# MOSFET.net
KiCad netlist of a schematic drawn in Altium Designer
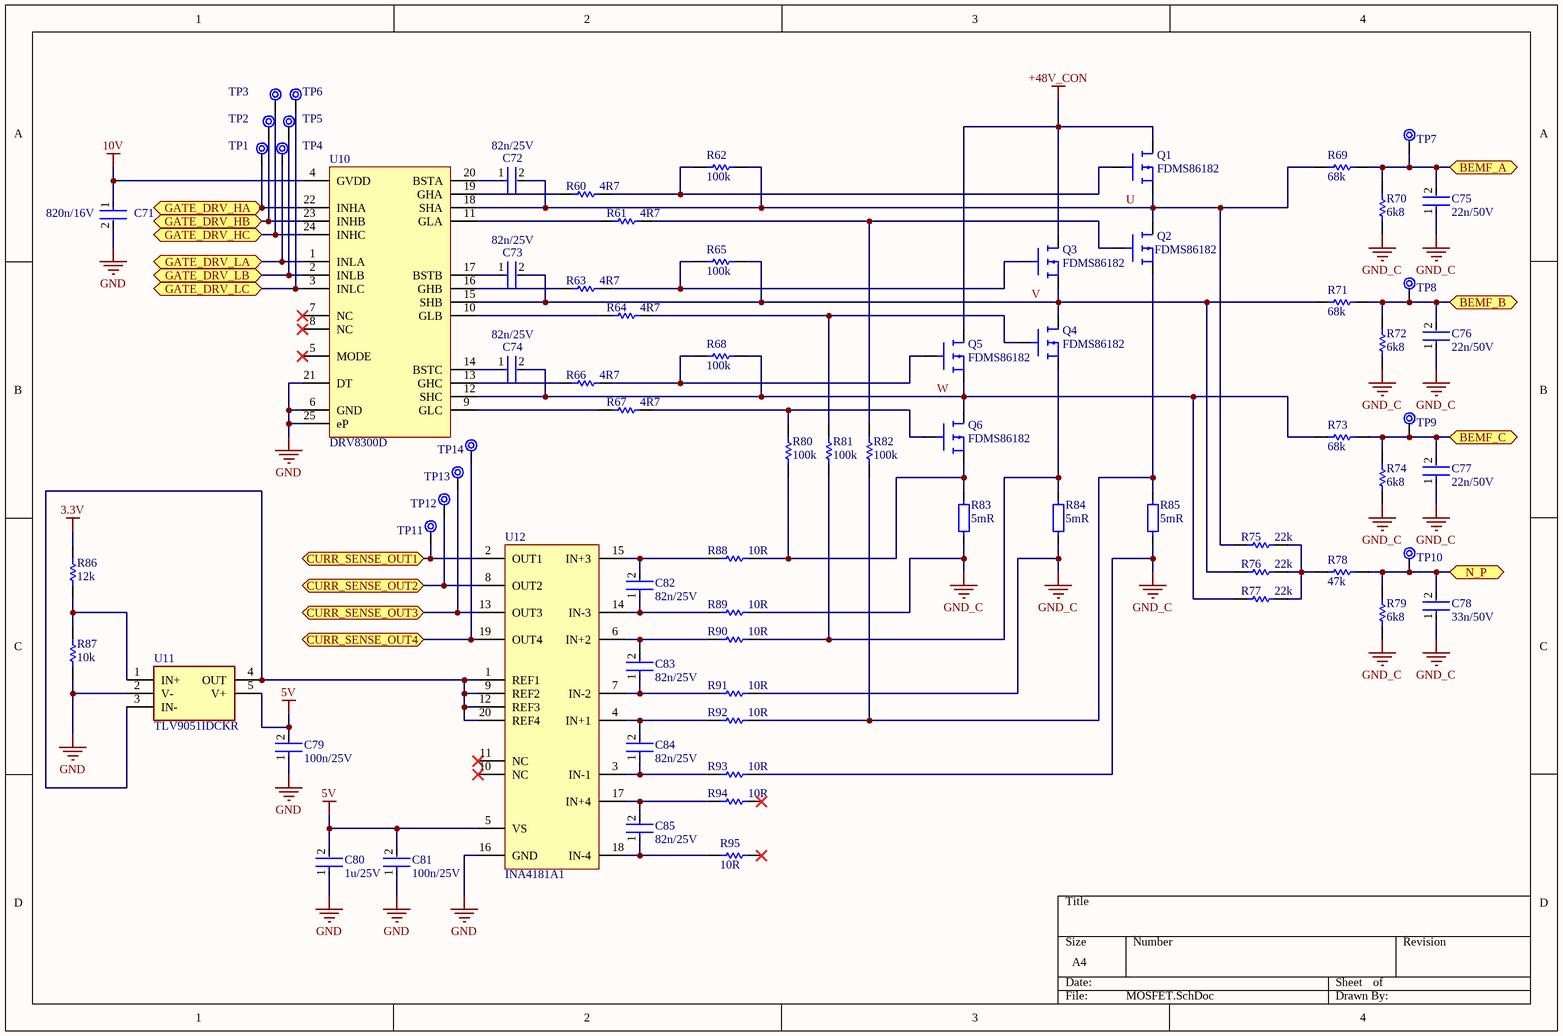
[diagram p0: MOSFET.SchDoc]

(export (version "E")
  (design (tool "Eeschema 10.0.6"))
  (components
    (comp (ref "C71")
      (value "820n/16V")
      (footprint "FP-C0805C-DN-MFG")
      (description "CAP CER 0.1UF 50V X7R 0805")
      (fields
        (field (name "MANUFACTURER PART NUMBER") "C0805C104K5RACTU")
        (field (name "MANUFACTURER") "KEMET")
      )
      (libsource (lib "Altium Content Vault") (part "b4654b650e69147ec39a6b967a45e02"))
    )
    (comp (ref "C72")
      (value "82n/25V")
      (footprint "FP-C0805C-DN-MFG")
      (description "CAP CER 0.1UF 50V X7R 0805")
      (fields
        (field (name "MANUFACTURER PART NUMBER") "C0805C104K5RACTU")
        (field (name "MANUFACTURER") "KEMET")
      )
      (libsource (lib "Altium Content Vault") (part "b4654b650e69147ec39a6b967a45e02"))
    )
    (comp (ref "C73")
      (value "82n/25V")
      (footprint "FP-C0805C-DN-MFG")
      (description "CAP CER 0.1UF 50V X7R 0805")
      (fields
        (field (name "MANUFACTURER PART NUMBER") "C0805C104K5RACTU")
        (field (name "MANUFACTURER") "KEMET")
      )
      (libsource (lib "Altium Content Vault") (part "b4654b650e69147ec39a6b967a45e02"))
    )
    (comp (ref "C74")
      (value "82n/25V")
      (footprint "FP-C0805C-DN-MFG")
      (description "CAP CER 0.1UF 50V X7R 0805")
      (fields
        (field (name "MANUFACTURER PART NUMBER") "C0805C104K5RACTU")
        (field (name "MANUFACTURER") "KEMET")
      )
      (libsource (lib "Altium Content Vault") (part "b4654b650e69147ec39a6b967a45e02"))
    )
    (comp (ref "C75")
      (value "22n/50V")
      (footprint "FP-C0805C-DN-MFG")
      (description "CAP CER 0.1UF 50V X7R 0805")
      (fields
        (field (name "MANUFACTURER PART NUMBER") "C0805C104K5RACTU")
        (field (name "MANUFACTURER") "KEMET")
      )
      (libsource (lib "Altium Content Vault") (part "b4654b650e69147ec39a6b967a45e02"))
    )
    (comp (ref "C76")
      (value "22n/50V")
      (footprint "FP-C0805C-DN-MFG")
      (description "CAP CER 0.1UF 50V X7R 0805")
      (fields
        (field (name "MANUFACTURER PART NUMBER") "C0805C104K5RACTU")
        (field (name "MANUFACTURER") "KEMET")
      )
      (libsource (lib "Altium Content Vault") (part "b4654b650e69147ec39a6b967a45e02"))
    )
    (comp (ref "C77")
      (value "22n/50V")
      (footprint "FP-C0805C-DN-MFG")
      (description "CAP CER 0.1UF 50V X7R 0805")
      (fields
        (field (name "MANUFACTURER PART NUMBER") "C0805C104K5RACTU")
        (field (name "MANUFACTURER") "KEMET")
      )
      (libsource (lib "Altium Content Vault") (part "b4654b650e69147ec39a6b967a45e02"))
    )
    (comp (ref "C78")
      (value "33n/50V")
      (footprint "FP-C0805C-DN-MFG")
      (description "CAP CER 0.1UF 50V X7R 0805")
      (fields
        (field (name "MANUFACTURER PART NUMBER") "C0805C104K5RACTU")
        (field (name "MANUFACTURER") "KEMET")
      )
      (libsource (lib "Altium Content Vault") (part "b4654b650e69147ec39a6b967a45e02"))
    )
    (comp (ref "C79")
      (value "100n/25V")
      (footprint "FP-C0805C-DN-MFG")
      (description "CAP CER 0.1UF 50V X7R 0805")
      (fields
        (field (name "MANUFACTURER PART NUMBER") "C0805C104K5RACTU")
        (field (name "MANUFACTURER") "KEMET")
      )
      (libsource (lib "Altium Content Vault") (part "b4654b650e69147ec39a6b967a45e02"))
    )
    (comp (ref "C80")
      (value "1u/25V")
      (footprint "FP-C0805C-DN-MFG")
      (description "CAP CER 0.1UF 50V X7R 0805")
      (fields
        (field (name "MANUFACTURER PART NUMBER") "C0805C104K5RACTU")
        (field (name "MANUFACTURER") "KEMET")
      )
      (libsource (lib "Altium Content Vault") (part "b4654b650e69147ec39a6b967a45e02"))
    )
    (comp (ref "C81")
      (value "100n/25V")
      (footprint "FP-C0805C-DN-MFG")
      (description "CAP CER 0.1UF 50V X7R 0805")
      (fields
        (field (name "MANUFACTURER PART NUMBER") "C0805C104K5RACTU")
        (field (name "MANUFACTURER") "KEMET")
      )
      (libsource (lib "Altium Content Vault") (part "b4654b650e69147ec39a6b967a45e02"))
    )
    (comp (ref "C82")
      (value "82n/25V")
      (footprint "FP-C0805C-DN-MFG")
      (description "CAP CER 0.1UF 50V X7R 0805")
      (fields
        (field (name "MANUFACTURER PART NUMBER") "C0805C104K5RACTU")
        (field (name "MANUFACTURER") "KEMET")
      )
      (libsource (lib "Altium Content Vault") (part "b4654b650e69147ec39a6b967a45e02"))
    )
    (comp (ref "C83")
      (value "82n/25V")
      (footprint "FP-C0805C-DN-MFG")
      (description "CAP CER 0.1UF 50V X7R 0805")
      (fields
        (field (name "MANUFACTURER PART NUMBER") "C0805C104K5RACTU")
        (field (name "MANUFACTURER") "KEMET")
      )
      (libsource (lib "Altium Content Vault") (part "b4654b650e69147ec39a6b967a45e02"))
    )
    (comp (ref "C84")
      (value "82n/25V")
      (footprint "FP-C0805C-DN-MFG")
      (description "CAP CER 0.1UF 50V X7R 0805")
      (fields
        (field (name "MANUFACTURER PART NUMBER") "C0805C104K5RACTU")
        (field (name "MANUFACTURER") "KEMET")
      )
      (libsource (lib "Altium Content Vault") (part "b4654b650e69147ec39a6b967a45e02"))
    )
    (comp (ref "C85")
      (value "82n/25V")
      (footprint "FP-C0805C-DN-MFG")
      (description "CAP CER 0.1UF 50V X7R 0805")
      (fields
        (field (name "MANUFACTURER PART NUMBER") "C0805C104K5RACTU")
        (field (name "MANUFACTURER") "KEMET")
      )
      (libsource (lib "Altium Content Vault") (part "b4654b650e69147ec39a6b967a45e02"))
    )
    (comp (ref "Q1")
      (value "FDMS86182")
      (footprint "FDMS86182")
      (description "MOSFET PTNG 100/20V Nch Power Trench MOSFET")
      (fields (field (name "MANUFACTURER") "Onsemi"))
      (libsource (lib "OTHER") (part "FDMS86182"))
    )
    (comp (ref "Q2")
      (value "FDMS86182")
      (footprint "FDMS86182")
      (description "MOSFET PTNG 100/20V Nch Power Trench MOSFET")
      (fields (field (name "MANUFACTURER") "Onsemi"))
      (libsource (lib "OTHER") (part "FDMS86182"))
    )
    (comp (ref "Q3")
      (value "FDMS86182")
      (footprint "FDMS86182")
      (description "MOSFET PTNG 100/20V Nch Power Trench MOSFET")
      (fields (field (name "MANUFACTURER") "Onsemi"))
      (libsource (lib "OTHER") (part "FDMS86182"))
    )
    (comp (ref "Q4")
      (value "FDMS86182")
      (footprint "FDMS86182")
      (description "MOSFET PTNG 100/20V Nch Power Trench MOSFET")
      (fields (field (name "MANUFACTURER") "Onsemi"))
      (libsource (lib "OTHER") (part "FDMS86182"))
    )
    (comp (ref "Q5")
      (value "FDMS86182")
      (footprint "FDMS86182")
      (description "MOSFET PTNG 100/20V Nch Power Trench MOSFET")
      (fields (field (name "MANUFACTURER") "Onsemi"))
      (libsource (lib "OTHER") (part "FDMS86182"))
    )
    (comp (ref "Q6")
      (value "FDMS86182")
      (footprint "FDMS86182")
      (description "MOSFET PTNG 100/20V Nch Power Trench MOSFET")
      (fields (field (name "MANUFACTURER") "Onsemi"))
      (libsource (lib "OTHER") (part "FDMS86182"))
    )
    (comp (ref "R60")
      (value "4R7")
      (footprint "RESC2013X50X30LL20T20")
      (description "0805")
      (fields (field (name "MANUFACTURER") "Vishay Dale") (field (name "PART NUMBER") "CRCW08050000Z0EA"))
      (libsource (lib "Altium Content Vault") (part "RES"))
    )
    (comp (ref "R61")
      (value "4R7")
      (footprint "RESC2013X50X30LL20T20")
      (description "0805")
      (fields (field (name "MANUFACTURER") "Vishay Dale") (field (name "PART NUMBER") "CRCW08050000Z0EA"))
      (libsource (lib "Altium Content Vault") (part "RES"))
    )
    (comp (ref "R62")
      (value "100k")
      (footprint "RESC2013X50X30LL20T20")
      (description "0805")
      (fields (field (name "MANUFACTURER") "Vishay Dale") (field (name "PART NUMBER") "CRCW08050000Z0EA"))
      (libsource (lib "Altium Content Vault") (part "RES"))
    )
    (comp (ref "R63")
      (value "4R7")
      (footprint "RESC2013X50X30LL20T20")
      (description "0805")
      (fields (field (name "MANUFACTURER") "Vishay Dale") (field (name "PART NUMBER") "CRCW08050000Z0EA"))
      (libsource (lib "Altium Content Vault") (part "RES"))
    )
    (comp (ref "R64")
      (value "4R7")
      (footprint "RESC2013X50X30LL20T20")
      (description "0805")
      (fields (field (name "MANUFACTURER") "Vishay Dale") (field (name "PART NUMBER") "CRCW08050000Z0EA"))
      (libsource (lib "Altium Content Vault") (part "RES"))
    )
    (comp (ref "R65")
      (value "100k")
      (footprint "RESC2013X50X30LL20T20")
      (description "0805")
      (fields (field (name "MANUFACTURER") "Vishay Dale") (field (name "PART NUMBER") "CRCW08050000Z0EA"))
      (libsource (lib "Altium Content Vault") (part "RES"))
    )
    (comp (ref "R66")
      (value "4R7")
      (footprint "RESC2013X50X30LL20T20")
      (description "0805")
      (fields (field (name "MANUFACTURER") "Vishay Dale") (field (name "PART NUMBER") "CRCW08050000Z0EA"))
      (libsource (lib "Altium Content Vault") (part "RES"))
    )
    (comp (ref "R67")
      (value "4R7")
      (footprint "RESC2013X50X30LL20T20")
      (description "0805")
      (fields (field (name "MANUFACTURER") "Vishay Dale") (field (name "PART NUMBER") "CRCW08050000Z0EA"))
      (libsource (lib "Altium Content Vault") (part "RES"))
    )
    (comp (ref "R68")
      (value "100k")
      (footprint "RESC2013X50X30LL20T20")
      (description "0805")
      (fields (field (name "MANUFACTURER") "Vishay Dale") (field (name "PART NUMBER") "CRCW08050000Z0EA"))
      (libsource (lib "Altium Content Vault") (part "RES"))
    )
    (comp (ref "R69")
      (value "68k")
      (footprint "RESC2013X50X30LL20T20")
      (description "0805")
      (fields (field (name "MANUFACTURER") "Vishay Dale") (field (name "PART NUMBER") "CRCW08050000Z0EA"))
      (libsource (lib "Altium Content Vault") (part "RES"))
    )
    (comp (ref "R70")
      (value "6k8")
      (footprint "RESC2013X50X30LL20T20")
      (description "0805")
      (fields (field (name "MANUFACTURER") "Vishay Dale") (field (name "PART NUMBER") "CRCW08050000Z0EA"))
      (libsource (lib "Altium Content Vault") (part "RES"))
    )
    (comp (ref "R71")
      (value "68k")
      (footprint "RESC2013X50X30LL20T20")
      (description "0805")
      (fields (field (name "MANUFACTURER") "Vishay Dale") (field (name "PART NUMBER") "CRCW08050000Z0EA"))
      (libsource (lib "Altium Content Vault") (part "RES"))
    )
    (comp (ref "R72")
      (value "6k8")
      (footprint "RESC2013X50X30LL20T20")
      (description "0805")
      (fields (field (name "MANUFACTURER") "Vishay Dale") (field (name "PART NUMBER") "CRCW08050000Z0EA"))
      (libsource (lib "Altium Content Vault") (part "RES"))
    )
    (comp (ref "R73")
      (value "68k")
      (footprint "RESC2013X50X30LL20T20")
      (description "0805")
      (fields (field (name "MANUFACTURER") "Vishay Dale") (field (name "PART NUMBER") "CRCW08050000Z0EA"))
      (libsource (lib "Altium Content Vault") (part "RES"))
    )
    (comp (ref "R74")
      (value "6k8")
      (footprint "RESC2013X50X30LL20T20")
      (description "0805")
      (fields (field (name "MANUFACTURER") "Vishay Dale") (field (name "PART NUMBER") "CRCW08050000Z0EA"))
      (libsource (lib "Altium Content Vault") (part "RES"))
    )
    (comp (ref "R75")
      (value "22k")
      (footprint "RESC2013X50X30LL20T20")
      (description "0805")
      (fields (field (name "MANUFACTURER") "Vishay Dale") (field (name "PART NUMBER") "CRCW08050000Z0EA"))
      (libsource (lib "Altium Content Vault") (part "RES"))
    )
    (comp (ref "R76")
      (value "22k")
      (footprint "RESC2013X50X30LL20T20")
      (description "0805")
      (fields (field (name "MANUFACTURER") "Vishay Dale") (field (name "PART NUMBER") "CRCW08050000Z0EA"))
      (libsource (lib "Altium Content Vault") (part "RES"))
    )
    (comp (ref "R77")
      (value "22k")
      (footprint "RESC2013X50X30LL20T20")
      (description "0805")
      (fields (field (name "MANUFACTURER") "Vishay Dale") (field (name "PART NUMBER") "CRCW08050000Z0EA"))
      (libsource (lib "Altium Content Vault") (part "RES"))
    )
    (comp (ref "R78")
      (value "47k")
      (footprint "RESC2013X50X30LL20T20")
      (description "0805")
      (fields (field (name "MANUFACTURER") "Vishay Dale") (field (name "PART NUMBER") "CRCW08050000Z0EA"))
      (libsource (lib "Altium Content Vault") (part "RES"))
    )
    (comp (ref "R79")
      (value "6k8")
      (footprint "RESC2013X50X30LL20T20")
      (description "0805")
      (fields (field (name "MANUFACTURER") "Vishay Dale") (field (name "PART NUMBER") "CRCW08050000Z0EA"))
      (libsource (lib "Altium Content Vault") (part "RES"))
    )
    (comp (ref "R80")
      (value "100k")
      (footprint "RESC2013X50X30LL20T20")
      (description "0805")
      (fields (field (name "MANUFACTURER") "Vishay Dale") (field (name "PART NUMBER") "CRCW08050000Z0EA"))
      (libsource (lib "Altium Content Vault") (part "RES"))
    )
    (comp (ref "R81")
      (value "100k")
      (footprint "RESC2013X50X30LL20T20")
      (description "0805")
      (fields (field (name "MANUFACTURER") "Vishay Dale") (field (name "PART NUMBER") "CRCW08050000Z0EA"))
      (libsource (lib "Altium Content Vault") (part "RES"))
    )
    (comp (ref "R82")
      (value "100k")
      (footprint "RESC2013X50X30LL20T20")
      (description "0805")
      (fields (field (name "MANUFACTURER") "Vishay Dale") (field (name "PART NUMBER") "CRCW08050000Z0EA"))
      (libsource (lib "Altium Content Vault") (part "RES"))
    )
    (comp (ref "R83")
      (value "5mR")
      (footprint "RESC6432X08N")
      (description "Current Sense Resistors - SMD 0.005ohms 1% 75PPM")
      (fields (field (name "MANUFACTURER") "Vishay") (field (name "PART NUMBER") "CRCW0402100RFKEDC"))
      (libsource (lib "RESISTOR") (part "RES/5mR/1%/2512"))
    )
    (comp (ref "R84")
      (value "5mR")
      (footprint "RESC6432X08N")
      (description "Current Sense Resistors - SMD 0.005ohms 1% 75PPM")
      (fields (field (name "MANUFACTURER") "Vishay") (field (name "PART NUMBER") "CRCW0402100RFKEDC"))
      (libsource (lib "RESISTOR") (part "RES/5mR/1%/2512"))
    )
    (comp (ref "R85")
      (value "5mR")
      (footprint "RESC6432X08N")
      (description "Current Sense Resistors - SMD 0.005ohms 1% 75PPM")
      (fields (field (name "MANUFACTURER") "Vishay") (field (name "PART NUMBER") "CRCW0402100RFKEDC"))
      (libsource (lib "RESISTOR") (part "RES/5mR/1%/2512"))
    )
    (comp (ref "R86")
      (value "12k")
      (footprint "RESC2013X50X30LL20T20")
      (description "0805")
      (fields (field (name "MANUFACTURER") "Vishay Dale") (field (name "PART NUMBER") "CRCW08050000Z0EA"))
      (libsource (lib "Altium Content Vault") (part "RES"))
    )
    (comp (ref "R87")
      (value "10k")
      (footprint "RESC2013X50X30LL20T20")
      (description "0805")
      (fields (field (name "MANUFACTURER") "Vishay Dale") (field (name "PART NUMBER") "CRCW08050000Z0EA"))
      (libsource (lib "Altium Content Vault") (part "RES"))
    )
    (comp (ref "R88")
      (value "10R")
      (footprint "RESC2013X50X30LL20T20")
      (description "0805")
      (fields (field (name "MANUFACTURER") "Vishay Dale") (field (name "PART NUMBER") "CRCW08050000Z0EA"))
      (libsource (lib "Altium Content Vault") (part "RES"))
    )
    (comp (ref "R89")
      (value "10R")
      (footprint "RESC2013X50X30LL20T20")
      (description "0805")
      (fields (field (name "MANUFACTURER") "Vishay Dale") (field (name "PART NUMBER") "CRCW08050000Z0EA"))
      (libsource (lib "Altium Content Vault") (part "RES"))
    )
    (comp (ref "R90")
      (value "10R")
      (footprint "RESC2013X50X30LL20T20")
      (description "0805")
      (fields (field (name "MANUFACTURER") "Vishay Dale") (field (name "PART NUMBER") "CRCW08050000Z0EA"))
      (libsource (lib "Altium Content Vault") (part "RES"))
    )
    (comp (ref "R91")
      (value "10R")
      (footprint "RESC2013X50X30LL20T20")
      (description "0805")
      (fields (field (name "MANUFACTURER") "Vishay Dale") (field (name "PART NUMBER") "CRCW08050000Z0EA"))
      (libsource (lib "Altium Content Vault") (part "RES"))
    )
    (comp (ref "R92")
      (value "10R")
      (footprint "RESC2013X50X30LL20T20")
      (description "0805")
      (fields (field (name "MANUFACTURER") "Vishay Dale") (field (name "PART NUMBER") "CRCW08050000Z0EA"))
      (libsource (lib "Altium Content Vault") (part "RES"))
    )
    (comp (ref "R93")
      (value "10R")
      (footprint "RESC2013X50X30LL20T20")
      (description "0805")
      (fields (field (name "MANUFACTURER") "Vishay Dale") (field (name "PART NUMBER") "CRCW08050000Z0EA"))
      (libsource (lib "Altium Content Vault") (part "RES"))
    )
    (comp (ref "R94")
      (value "10R")
      (footprint "RESC2013X50X30LL20T20")
      (description "0805")
      (fields (field (name "MANUFACTURER") "Vishay Dale") (field (name "PART NUMBER") "CRCW08050000Z0EA"))
      (libsource (lib "Altium Content Vault") (part "RES"))
    )
    (comp (ref "R95")
      (value "10R")
      (footprint "RESC2013X50X30LL20T20")
      (description "0805")
      (fields (field (name "MANUFACTURER") "Vishay Dale") (field (name "PART NUMBER") "CRCW08050000Z0EA"))
      (libsource (lib "Altium Content Vault") (part "RES"))
    )
    (comp (ref "TP1")
      (value "Test Point 1mm")
      (footprint "Pad 1mm")
      (libsource (lib "OTHER") (part "Test Point 1mm"))
    )
    (comp (ref "TP2")
      (value "Test Point 1mm")
      (footprint "Pad 1mm")
      (libsource (lib "OTHER") (part "Test Point 1mm"))
    )
    (comp (ref "TP3")
      (value "Test Point 1mm")
      (footprint "Pad 1mm")
      (libsource (lib "OTHER") (part "Test Point 1mm"))
    )
    (comp (ref "TP4")
      (value "Test Point 1mm")
      (footprint "Pad 1mm")
      (libsource (lib "OTHER") (part "Test Point 1mm"))
    )
    (comp (ref "TP5")
      (value "Test Point 1mm")
      (footprint "Pad 1mm")
      (libsource (lib "OTHER") (part "Test Point 1mm"))
    )
    (comp (ref "TP6")
      (value "Test Point 1mm")
      (footprint "Pad 1mm")
      (libsource (lib "OTHER") (part "Test Point 1mm"))
    )
    (comp (ref "TP7")
      (value "Test Point 1mm")
      (footprint "Pad 1mm")
      (libsource (lib "OTHER") (part "Test Point 1mm"))
    )
    (comp (ref "TP8")
      (value "Test Point 1mm")
      (footprint "Pad 1mm")
      (libsource (lib "OTHER") (part "Test Point 1mm"))
    )
    (comp (ref "TP9")
      (value "Test Point 1mm")
      (footprint "Pad 1mm")
      (libsource (lib "OTHER") (part "Test Point 1mm"))
    )
    (comp (ref "TP10")
      (value "Test Point 1mm")
      (footprint "Pad 1mm")
      (libsource (lib "OTHER") (part "Test Point 1mm"))
    )
    (comp (ref "TP11")
      (value "Test Point 1mm")
      (footprint "Pad 1mm")
      (libsource (lib "OTHER") (part "Test Point 1mm"))
    )
    (comp (ref "TP12")
      (value "Test Point 1mm")
      (footprint "Pad 1mm")
      (libsource (lib "OTHER") (part "Test Point 1mm"))
    )
    (comp (ref "TP13")
      (value "Test Point 1mm")
      (footprint "Pad 1mm")
      (libsource (lib "OTHER") (part "Test Point 1mm"))
    )
    (comp (ref "TP14")
      (value "Test Point 1mm")
      (footprint "Pad 1mm")
      (libsource (lib "OTHER") (part "Test Point 1mm"))
    )
    (comp (ref "U10")
      (value "DRV8300D")
      (footprint "PQFN50P400X400X100_HS-25N")
      (description "Gate Drivers 100-V max simple 3-phase gate driver with bootstrap diodes 24-VQFN -40 to 125")
      (fields (field (name "MANUFACTURER") "Texas Instruments") (field (name "PART NUMBER") "DRV8300DRGER"))
      (libsource (lib "IC") (part "DRV8300D"))
    )
    (comp (ref "U11")
      (value "TLV9051IDCKR")
      (footprint "SOT65P210X110-5N")
      (description "Operational Amplifiers - Op Amps OPAMP")
      (fields (field (name "MOUSER PART NUMBER") "595-TLV9051IDCKR"))
      (libsource (lib "TLV9051IDCKR_LeveLConv") (part "TLV9051IDCKR"))
    )
    (comp (ref "U12")
      (value "INA4181A1")
      (footprint "TSOP65P640X120-20N")
      (fields (field (name "MANUFACTURER") "Texas Instruments") (field (name "PART NUMBER") "INA4181A1IPWR"))
      (libsource (lib "IC") (part "INA4181A1"))
    )
  )
  (nets
    (net (code "1") (name "+48V_CON") (class "Default")
      (node (ref "Q1") (pin "D") (pinfunction "D_D") (pintype "passive"))
      (node (ref "Q3") (pin "D") (pinfunction "D_D") (pintype "passive"))
      (node (ref "Q5") (pin "D") (pinfunction "D_D") (pintype "passive"))
    )
    (net (code "2") (name "/BEMF_A") (class "Default")
      (node (ref "C75") (pin "2") (pinfunction "2_2") (pintype "passive"))
      (node (ref "R69") (pin "1") (pinfunction "1_1") (pintype "passive"))
      (node (ref "R70") (pin "1") (pinfunction "1_1") (pintype "passive"))
      (node (ref "TP7") (pin "1") (pinfunction "1_1") (pintype "passive"))
    )
    (net (code "3") (name "/BEMF_B") (class "Default")
      (node (ref "C76") (pin "2") (pinfunction "2_2") (pintype "passive"))
      (node (ref "R71") (pin "1") (pinfunction "1_1") (pintype "passive"))
      (node (ref "R72") (pin "1") (pinfunction "1_1") (pintype "passive"))
      (node (ref "TP8") (pin "1") (pinfunction "1_1") (pintype "passive"))
    )
    (net (code "4") (name "/BEMF_C") (class "Default")
      (node (ref "C77") (pin "2") (pinfunction "2_2") (pintype "passive"))
      (node (ref "R73") (pin "1") (pinfunction "1_1") (pintype "passive"))
      (node (ref "R74") (pin "1") (pinfunction "1_1") (pintype "passive"))
      (node (ref "TP9") (pin "1") (pinfunction "1_1") (pintype "passive"))
    )
    (net (code "5") (name "/CURR_SENSE_OUT1") (class "Default")
      (node (ref "TP11") (pin "1") (pinfunction "1_1") (pintype "passive"))
      (node (ref "U12") (pin "2") (pinfunction "OUT1_2") (pintype "passive"))
    )
    (net (code "6") (name "/CURR_SENSE_OUT2") (class "Default")
      (node (ref "TP12") (pin "1") (pinfunction "1_1") (pintype "passive"))
      (node (ref "U12") (pin "8") (pinfunction "OUT2_8") (pintype "passive"))
    )
    (net (code "7") (name "/CURR_SENSE_OUT3") (class "Default")
      (node (ref "TP13") (pin "1") (pinfunction "1_1") (pintype "passive"))
      (node (ref "U12") (pin "13") (pinfunction "OUT3_13") (pintype "passive"))
    )
    (net (code "8") (name "/CURR_SENSE_OUT4") (class "Default")
      (node (ref "TP14") (pin "1") (pinfunction "1_1") (pintype "passive"))
      (node (ref "U12") (pin "19") (pinfunction "OUT4_19") (pintype "passive"))
    )
    (net (code "9") (name "/GATE_DRV_HA") (class "Default")
      (node (ref "TP1") (pin "1") (pinfunction "1_1") (pintype "passive"))
      (node (ref "U10") (pin "22") (pinfunction "INHA_22") (pintype "passive"))
    )
    (net (code "10") (name "/GATE_DRV_HB") (class "Default")
      (node (ref "TP2") (pin "1") (pinfunction "1_1") (pintype "passive"))
      (node (ref "U10") (pin "23") (pinfunction "INHB_23") (pintype "passive"))
    )
    (net (code "11") (name "/GATE_DRV_HC") (class "Default")
      (node (ref "TP3") (pin "1") (pinfunction "1_1") (pintype "passive"))
      (node (ref "U10") (pin "24") (pinfunction "INHC_24") (pintype "passive"))
    )
    (net (code "12") (name "/GATE_DRV_LA") (class "Default")
      (node (ref "TP4") (pin "1") (pinfunction "1_1") (pintype "passive"))
      (node (ref "U10") (pin "1") (pinfunction "INLA_1") (pintype "passive"))
    )
    (net (code "13") (name "/GATE_DRV_LB") (class "Default")
      (node (ref "TP5") (pin "1") (pinfunction "1_1") (pintype "passive"))
      (node (ref "U10") (pin "2") (pinfunction "INLB_2") (pintype "passive"))
    )
    (net (code "14") (name "/GATE_DRV_LC") (class "Default")
      (node (ref "TP6") (pin "1") (pinfunction "1_1") (pintype "passive"))
      (node (ref "U10") (pin "3") (pinfunction "INLC_3") (pintype "passive"))
    )
    (net (code "15") (name "/N_P") (class "Default")
      (node (ref "C78") (pin "2") (pinfunction "2_2") (pintype "passive"))
      (node (ref "R78") (pin "1") (pinfunction "1_1") (pintype "passive"))
      (node (ref "R79") (pin "1") (pinfunction "1_1") (pintype "passive"))
      (node (ref "TP10") (pin "1") (pinfunction "1_1") (pintype "passive"))
    )
    (net (code "16") (name "/U") (class "Default")
      (node (ref "C72") (pin "2") (pinfunction "2_2") (pintype "passive"))
      (node (ref "Q1") (pin "S") (pinfunction "S_S") (pintype "passive"))
      (node (ref "Q2") (pin "D") (pinfunction "D_D") (pintype "passive"))
      (node (ref "R62") (pin "1") (pinfunction "1_1") (pintype "passive"))
      (node (ref "R69") (pin "2") (pinfunction "2_2") (pintype "passive"))
      (node (ref "R75") (pin "2") (pinfunction "2_2") (pintype "passive"))
      (node (ref "U10") (pin "18") (pinfunction "SHA_18") (pintype "passive"))
    )
    (net (code "17") (name "/V") (class "Default")
      (node (ref "C73") (pin "2") (pinfunction "2_2") (pintype "passive"))
      (node (ref "Q3") (pin "S") (pinfunction "S_S") (pintype "passive"))
      (node (ref "Q4") (pin "D") (pinfunction "D_D") (pintype "passive"))
      (node (ref "R65") (pin "1") (pinfunction "1_1") (pintype "passive"))
      (node (ref "R71") (pin "2") (pinfunction "2_2") (pintype "passive"))
      (node (ref "R76") (pin "2") (pinfunction "2_2") (pintype "passive"))
      (node (ref "U10") (pin "15") (pinfunction "SHB_15") (pintype "passive"))
    )
    (net (code "18") (name "/W") (class "Default")
      (node (ref "C74") (pin "2") (pinfunction "2_2") (pintype "passive"))
      (node (ref "Q5") (pin "S") (pinfunction "S_S") (pintype "passive"))
      (node (ref "Q6") (pin "D") (pinfunction "D_D") (pintype "passive"))
      (node (ref "R68") (pin "1") (pinfunction "1_1") (pintype "passive"))
      (node (ref "R73") (pin "2") (pinfunction "2_2") (pintype "passive"))
      (node (ref "R77") (pin "2") (pinfunction "2_2") (pintype "passive"))
      (node (ref "U10") (pin "12") (pinfunction "SHC_12") (pintype "passive"))
    )
    (net (code "19") (name "3.3V") (class "Default")
      (node (ref "R86") (pin "1") (pinfunction "1_1") (pintype "passive"))
    )
    (net (code "20") (name "5V") (class "Default")
      (node (ref "C79") (pin "2") (pinfunction "2_2") (pintype "passive"))
      (node (ref "C80") (pin "2") (pinfunction "2_2") (pintype "passive"))
      (node (ref "C81") (pin "2") (pinfunction "2_2") (pintype "passive"))
      (node (ref "U11") (pin "5") (pinfunction "V+_5") (pintype "passive"))
      (node (ref "U12") (pin "5") (pinfunction "VS_5") (pintype "passive"))
    )
    (net (code "21") (name "10V") (class "Default")
      (node (ref "C71") (pin "1") (pinfunction "1_1") (pintype "passive"))
      (node (ref "U10") (pin "4") (pinfunction "GVDD_4") (pintype "passive"))
    )
    (net (code "22") (name "GND") (class "Default")
      (node (ref "C71") (pin "2") (pinfunction "2_2") (pintype "passive"))
      (node (ref "C79") (pin "1") (pinfunction "1_1") (pintype "passive"))
      (node (ref "C80") (pin "1") (pinfunction "1_1") (pintype "passive"))
      (node (ref "C81") (pin "1") (pinfunction "1_1") (pintype "passive"))
      (node (ref "R87") (pin "2") (pinfunction "2_2") (pintype "passive"))
      (node (ref "U10") (pin "21") (pinfunction "DT_21") (pintype "passive"))
      (node (ref "U10") (pin "25") (pinfunction "eP_25") (pintype "passive"))
      (node (ref "U10") (pin "6") (pinfunction "GND_6") (pintype "passive"))
      (node (ref "U11") (pin "2") (pinfunction "V-_2") (pintype "passive"))
      (node (ref "U12") (pin "16") (pinfunction "GND_16") (pintype "passive"))
    )
    (net (code "23") (name "GND_C") (class "Default")
      (node (ref "C75") (pin "1") (pinfunction "1_1") (pintype "passive"))
      (node (ref "C76") (pin "1") (pinfunction "1_1") (pintype "passive"))
      (node (ref "C77") (pin "1") (pinfunction "1_1") (pintype "passive"))
      (node (ref "C78") (pin "1") (pinfunction "1_1") (pintype "passive"))
      (node (ref "R70") (pin "2") (pinfunction "2_2") (pintype "passive"))
      (node (ref "R72") (pin "2") (pinfunction "2_2") (pintype "passive"))
      (node (ref "R74") (pin "2") (pinfunction "2_2") (pintype "passive"))
      (node (ref "R79") (pin "2") (pinfunction "2_2") (pintype "passive"))
      (node (ref "R83") (pin "1") (pinfunction "1_1") (pintype "passive"))
      (node (ref "R84") (pin "1") (pinfunction "1_1") (pintype "passive"))
      (node (ref "R85") (pin "1") (pinfunction "1_1") (pintype "passive"))
      (node (ref "R89") (pin "1") (pinfunction "1_1") (pintype "passive"))
      (node (ref "R91") (pin "1") (pinfunction "1_1") (pintype "passive"))
      (node (ref "R93") (pin "1") (pinfunction "1_1") (pintype "passive"))
    )
    (net (code "24") (name "Net-(Q1-PadG)") (class "Default")
      (node (ref "Q1") (pin "G") (pinfunction "G_G") (pintype "passive"))
      (node (ref "R60") (pin "1") (pinfunction "1_1") (pintype "passive"))
      (node (ref "R62") (pin "2") (pinfunction "2_2") (pintype "passive"))
    )
    (net (code "25") (name "Net-(Q2-PadG)") (class "Default")
      (node (ref "Q2") (pin "G") (pinfunction "G_G") (pintype "passive"))
      (node (ref "R61") (pin "1") (pinfunction "1_1") (pintype "passive"))
      (node (ref "R82") (pin "1") (pinfunction "1_1") (pintype "passive"))
    )
    (net (code "26") (name "Net-(Q2-PadS)") (class "Default")
      (node (ref "Q2") (pin "S") (pinfunction "S_S") (pintype "passive"))
      (node (ref "R82") (pin "2") (pinfunction "2_2") (pintype "passive"))
      (node (ref "R85") (pin "2") (pinfunction "2_2") (pintype "passive"))
      (node (ref "R92") (pin "1") (pinfunction "1_1") (pintype "passive"))
    )
    (net (code "27") (name "Net-(Q3-PadG)") (class "Default")
      (node (ref "Q3") (pin "G") (pinfunction "G_G") (pintype "passive"))
      (node (ref "R63") (pin "1") (pinfunction "1_1") (pintype "passive"))
      (node (ref "R65") (pin "2") (pinfunction "2_2") (pintype "passive"))
    )
    (net (code "28") (name "Net-(Q4-PadG)") (class "Default")
      (node (ref "Q4") (pin "G") (pinfunction "G_G") (pintype "passive"))
      (node (ref "R64") (pin "1") (pinfunction "1_1") (pintype "passive"))
      (node (ref "R81") (pin "1") (pinfunction "1_1") (pintype "passive"))
    )
    (net (code "29") (name "Net-(Q4-PadS)") (class "Default")
      (node (ref "Q4") (pin "S") (pinfunction "S_S") (pintype "passive"))
      (node (ref "R81") (pin "2") (pinfunction "2_2") (pintype "passive"))
      (node (ref "R84") (pin "2") (pinfunction "2_2") (pintype "passive"))
      (node (ref "R90") (pin "1") (pinfunction "1_1") (pintype "passive"))
    )
    (net (code "30") (name "Net-(Q5-PadG)") (class "Default")
      (node (ref "Q5") (pin "G") (pinfunction "G_G") (pintype "passive"))
      (node (ref "R66") (pin "1") (pinfunction "1_1") (pintype "passive"))
      (node (ref "R68") (pin "2") (pinfunction "2_2") (pintype "passive"))
    )
    (net (code "31") (name "Net-(Q6-PadG)") (class "Default")
      (node (ref "Q6") (pin "G") (pinfunction "G_G") (pintype "passive"))
      (node (ref "R67") (pin "1") (pinfunction "1_1") (pintype "passive"))
      (node (ref "R80") (pin "1") (pinfunction "1_1") (pintype "passive"))
    )
    (net (code "32") (name "Net-(Q6-PadS)") (class "Default")
      (node (ref "Q6") (pin "S") (pinfunction "S_S") (pintype "passive"))
      (node (ref "R80") (pin "2") (pinfunction "2_2") (pintype "passive"))
      (node (ref "R83") (pin "2") (pinfunction "2_2") (pintype "passive"))
      (node (ref "R88") (pin "1") (pinfunction "1_1") (pintype "passive"))
    )
    (net (code "33") (name "Net-(R75-Pad1)") (class "Default")
      (node (ref "R75") (pin "1") (pinfunction "1_1") (pintype "passive"))
      (node (ref "R76") (pin "1") (pinfunction "1_1") (pintype "passive"))
      (node (ref "R77") (pin "1") (pinfunction "1_1") (pintype "passive"))
      (node (ref "R78") (pin "2") (pinfunction "2_2") (pintype "passive"))
    )
    (net (code "34") (name "Net-(U10-BSTA)") (class "Default")
      (node (ref "C72") (pin "1") (pinfunction "1_1") (pintype "passive"))
      (node (ref "U10") (pin "20") (pinfunction "BSTA_20") (pintype "passive"))
    )
    (net (code "35") (name "Net-(U10-BSTB)") (class "Default")
      (node (ref "C73") (pin "1") (pinfunction "1_1") (pintype "passive"))
      (node (ref "U10") (pin "17") (pinfunction "BSTB_17") (pintype "passive"))
    )
    (net (code "36") (name "Net-(U10-BSTC)") (class "Default")
      (node (ref "C74") (pin "1") (pinfunction "1_1") (pintype "passive"))
      (node (ref "U10") (pin "14") (pinfunction "BSTC_14") (pintype "passive"))
    )
    (net (code "37") (name "Net-(U10-GHA)") (class "Default")
      (node (ref "R60") (pin "2") (pinfunction "2_2") (pintype "passive"))
      (node (ref "U10") (pin "19") (pinfunction "GHA_19") (pintype "passive"))
    )
    (net (code "38") (name "Net-(U10-GHB)") (class "Default")
      (node (ref "R63") (pin "2") (pinfunction "2_2") (pintype "passive"))
      (node (ref "U10") (pin "16") (pinfunction "GHB_16") (pintype "passive"))
    )
    (net (code "39") (name "Net-(U10-GHC)") (class "Default")
      (node (ref "R66") (pin "2") (pinfunction "2_2") (pintype "passive"))
      (node (ref "U10") (pin "13") (pinfunction "GHC_13") (pintype "passive"))
    )
    (net (code "40") (name "Net-(U10-GLA)") (class "Default")
      (node (ref "R61") (pin "2") (pinfunction "2_2") (pintype "passive"))
      (node (ref "U10") (pin "11") (pinfunction "GLA_11") (pintype "passive"))
    )
    (net (code "41") (name "Net-(U10-GLB)") (class "Default")
      (node (ref "R64") (pin "2") (pinfunction "2_2") (pintype "passive"))
      (node (ref "U10") (pin "10") (pinfunction "GLB_10") (pintype "passive"))
    )
    (net (code "42") (name "Net-(U10-GLC)") (class "Default")
      (node (ref "R67") (pin "2") (pinfunction "2_2") (pintype "passive"))
      (node (ref "U10") (pin "9") (pinfunction "GLC_9") (pintype "passive"))
    )
    (net (code "43") (name "Net-(U11-IN+)") (class "Default")
      (node (ref "R86") (pin "2") (pinfunction "2_2") (pintype "passive"))
      (node (ref "R87") (pin "1") (pinfunction "1_1") (pintype "passive"))
      (node (ref "U11") (pin "1") (pinfunction "IN+_1") (pintype "passive"))
    )
    (net (code "44") (name "Net-(U11-IN-)") (class "Default")
      (node (ref "U11") (pin "3") (pinfunction "IN-_3") (pintype "passive"))
      (node (ref "U11") (pin "4") (pinfunction "OUT_4") (pintype "passive"))
      (node (ref "U12") (pin "1") (pinfunction "REF1_1") (pintype "passive"))
      (node (ref "U12") (pin "12") (pinfunction "REF3_12") (pintype "passive"))
      (node (ref "U12") (pin "20") (pinfunction "REF4_20") (pintype "passive"))
      (node (ref "U12") (pin "9") (pinfunction "REF2_9") (pintype "passive"))
    )
    (net (code "45") (name "Net-(U12-IN+1)") (class "Default")
      (node (ref "C84") (pin "2") (pinfunction "2_2") (pintype "passive"))
      (node (ref "R92") (pin "2") (pinfunction "2_2") (pintype "passive"))
      (node (ref "U12") (pin "4") (pinfunction "IN+1_4") (pintype "passive"))
    )
    (net (code "46") (name "Net-(U12-IN+2)") (class "Default")
      (node (ref "C83") (pin "2") (pinfunction "2_2") (pintype "passive"))
      (node (ref "R90") (pin "2") (pinfunction "2_2") (pintype "passive"))
      (node (ref "U12") (pin "6") (pinfunction "IN+2_6") (pintype "passive"))
    )
    (net (code "47") (name "Net-(U12-IN+3)") (class "Default")
      (node (ref "C82") (pin "2") (pinfunction "2_2") (pintype "passive"))
      (node (ref "R88") (pin "2") (pinfunction "2_2") (pintype "passive"))
      (node (ref "U12") (pin "15") (pinfunction "IN+3_15") (pintype "passive"))
    )
    (net (code "48") (name "Net-(U12-IN+4)") (class "Default")
      (node (ref "C85") (pin "2") (pinfunction "2_2") (pintype "passive"))
      (node (ref "R94") (pin "2") (pinfunction "2_2") (pintype "passive"))
      (node (ref "U12") (pin "17") (pinfunction "IN+4_17") (pintype "passive"))
    )
    (net (code "49") (name "Net-(U12-IN-1)") (class "Default")
      (node (ref "C84") (pin "1") (pinfunction "1_1") (pintype "passive"))
      (node (ref "R93") (pin "2") (pinfunction "2_2") (pintype "passive"))
      (node (ref "U12") (pin "3") (pinfunction "IN-1_3") (pintype "passive"))
    )
    (net (code "50") (name "Net-(U12-IN-2)") (class "Default")
      (node (ref "C83") (pin "1") (pinfunction "1_1") (pintype "passive"))
      (node (ref "R91") (pin "2") (pinfunction "2_2") (pintype "passive"))
      (node (ref "U12") (pin "7") (pinfunction "IN-2_7") (pintype "passive"))
    )
    (net (code "51") (name "Net-(U12-IN-3)") (class "Default")
      (node (ref "C82") (pin "1") (pinfunction "1_1") (pintype "passive"))
      (node (ref "R89") (pin "2") (pinfunction "2_2") (pintype "passive"))
      (node (ref "U12") (pin "14") (pinfunction "IN-3_14") (pintype "passive"))
    )
    (net (code "52") (name "Net-(U12-IN-4)") (class "Default")
      (node (ref "C85") (pin "1") (pinfunction "1_1") (pintype "passive"))
      (node (ref "R95") (pin "2") (pinfunction "2_2") (pintype "passive"))
      (node (ref "U12") (pin "18") (pinfunction "IN-4_18") (pintype "passive"))
    )
    (net (code "53") (name "unconnected-(R94-Pad1)") (class "Default")
      (node (ref "R94") (pin "1") (pinfunction "1_1") (pintype "passive+no_connect"))
    )
    (net (code "54") (name "unconnected-(R95-Pad1)") (class "Default")
      (node (ref "R95") (pin "1") (pinfunction "1_1") (pintype "passive+no_connect"))
    )
    (net (code "55") (name "unconnected-(U10-MODE-Pad5)") (class "Default")
      (node (ref "U10") (pin "5") (pinfunction "MODE_5") (pintype "passive+no_connect"))
    )
    (net (code "56") (name "unconnected-(U10-NC-Pad7)") (class "Default")
      (node (ref "U10") (pin "7") (pinfunction "NC_7") (pintype "passive+no_connect"))
    )
    (net (code "57") (name "unconnected-(U10-NC-Pad8)") (class "Default")
      (node (ref "U10") (pin "8") (pinfunction "NC_8") (pintype "passive+no_connect"))
    )
    (net (code "58") (name "unconnected-(U12-NC-Pad10)") (class "Default")
      (node (ref "U12") (pin "10") (pinfunction "NC_10") (pintype "passive+no_connect"))
    )
    (net (code "59") (name "unconnected-(U12-NC-Pad11)") (class "Default")
      (node (ref "U12") (pin "11") (pinfunction "NC_11") (pintype "passive+no_connect"))
    )
  )
)
